# MCU176_2.net
KiCad netlist of a schematic drawn in Altium Designer
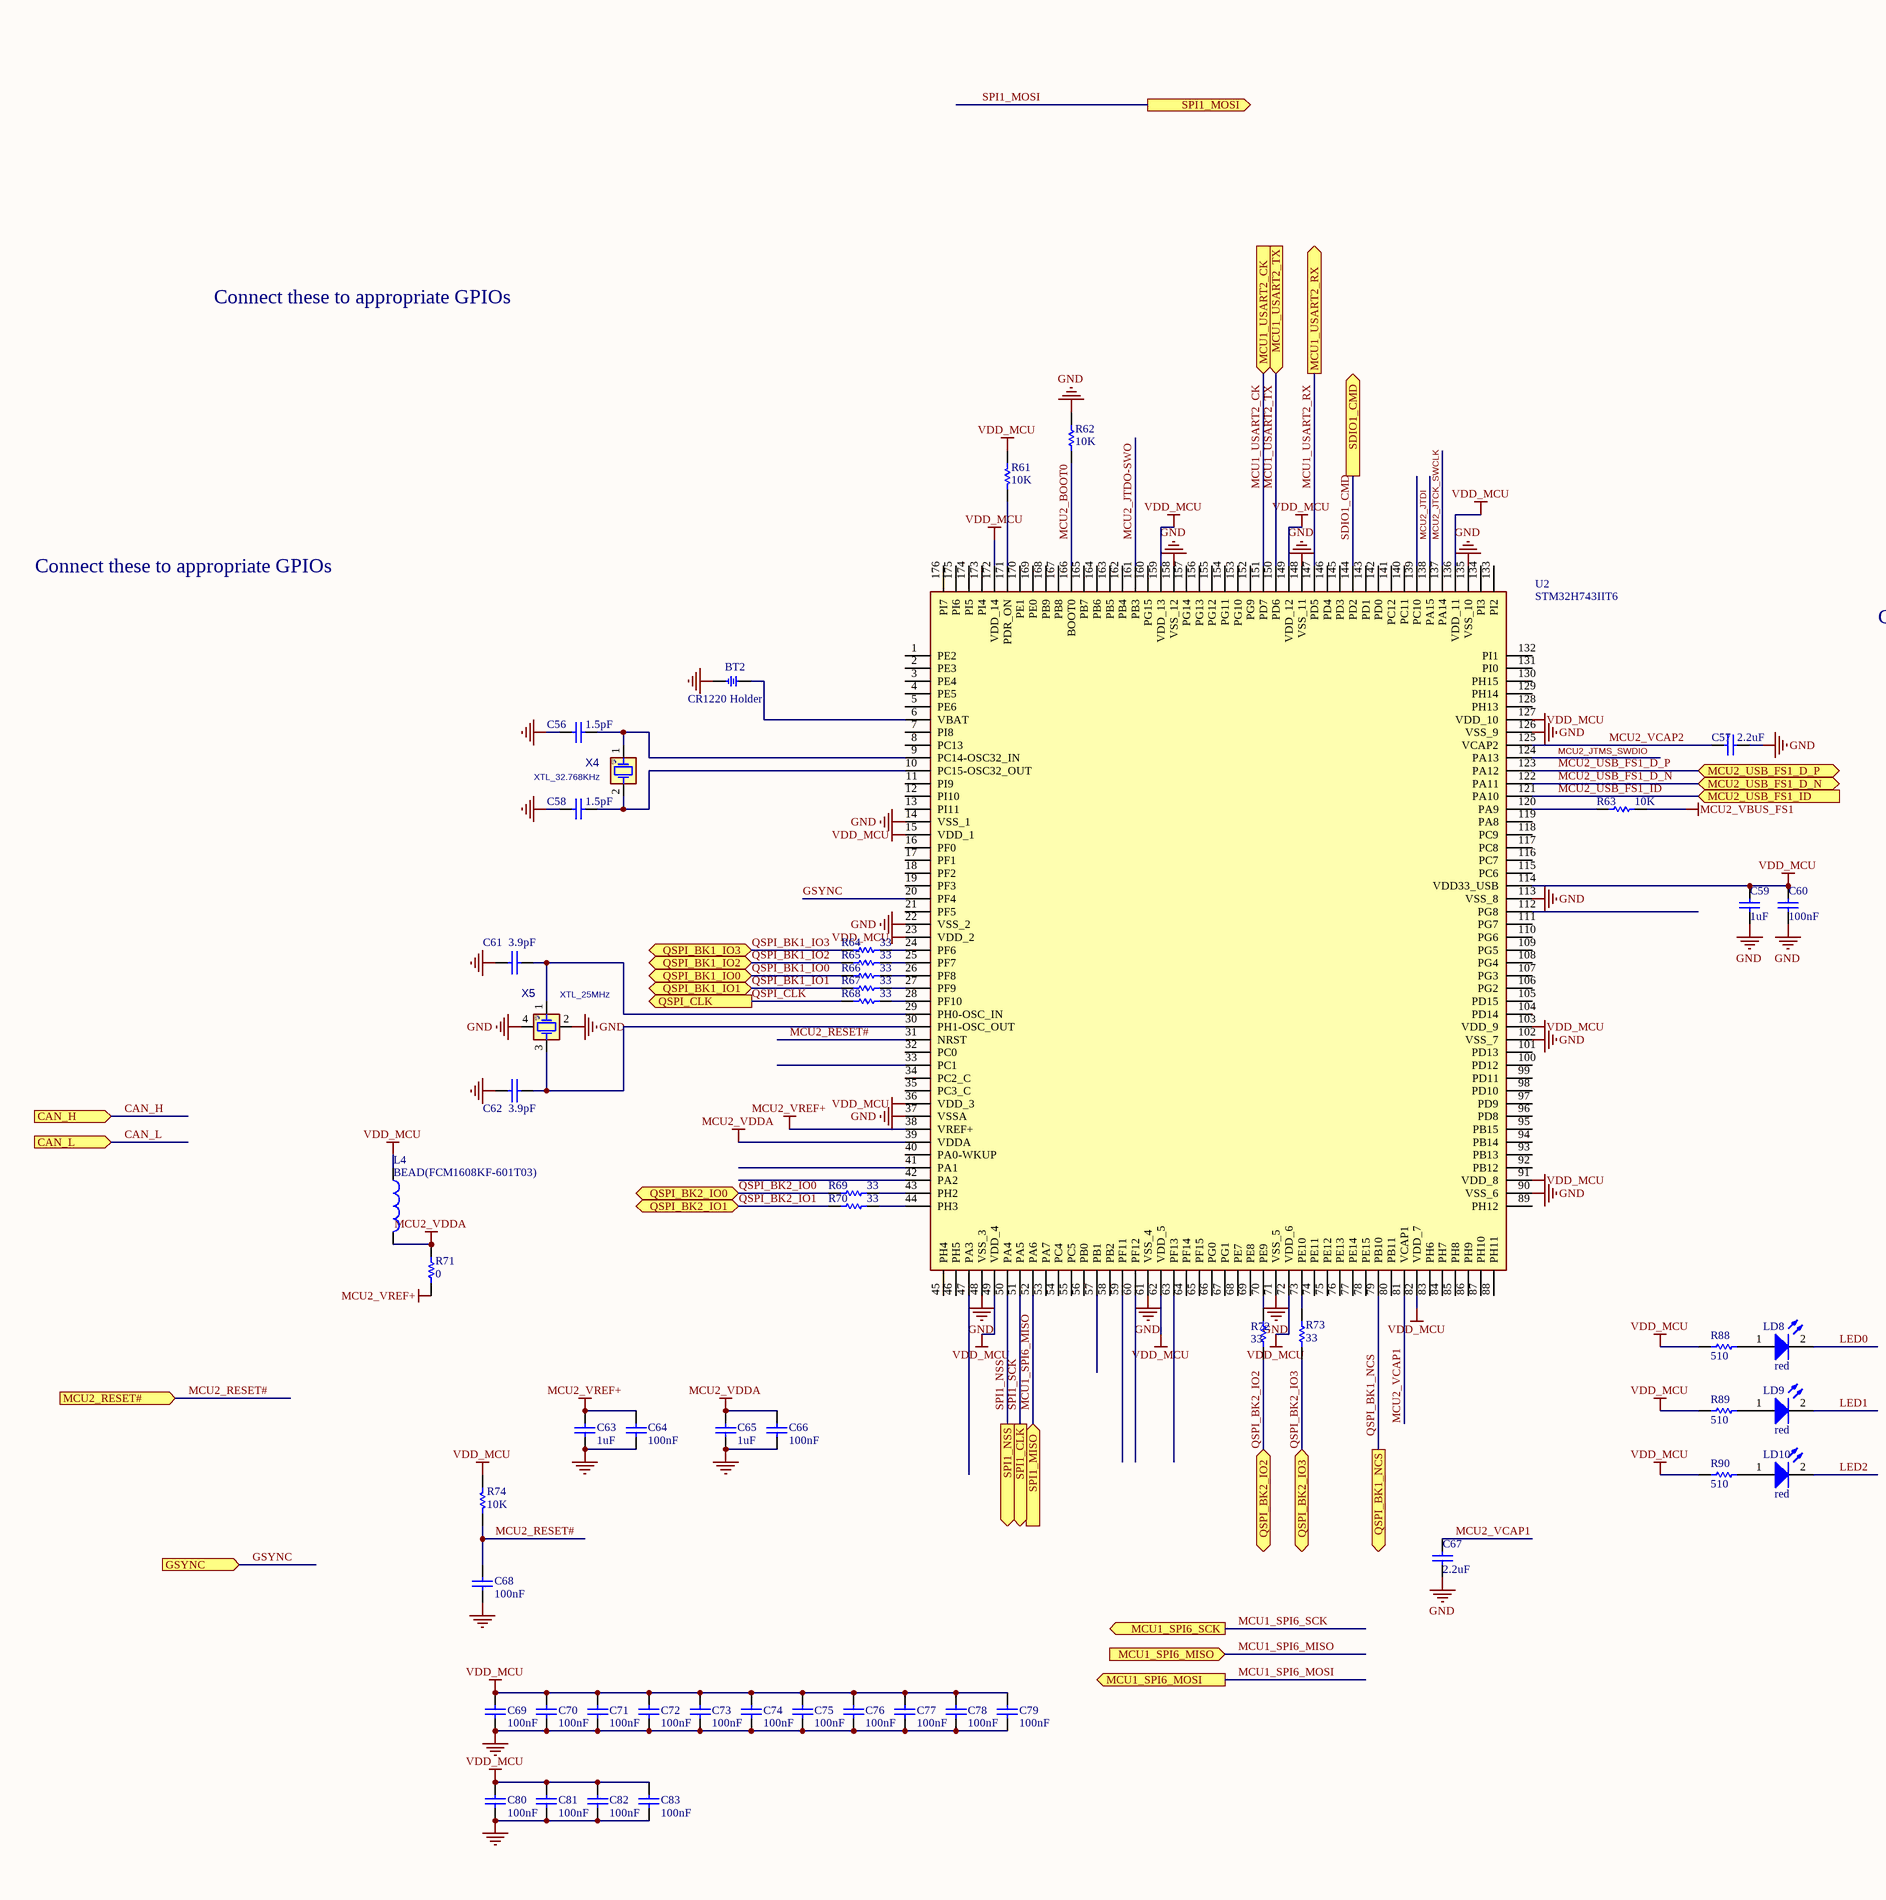
[diagram p0: MCU176_2.SchDoc, left]
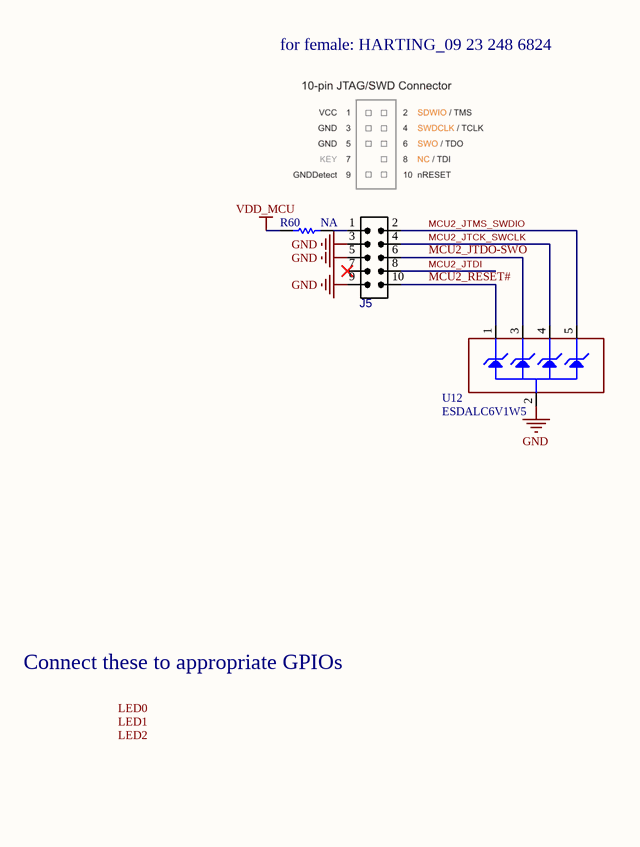
[diagram p1: MCU176_2.SchDoc, right]

(export (version "E")
  (design (tool "Eeschema 10.0.6"))
  (components
    (comp (ref "BT2")
      (value "CR1220 Holder")
      (footprint "BTH1220")
      (description "BATTERY HOLDER, CR1220")
      (libsource (lib "battery") (part "BATH_CR1220"))
    )
    (comp (ref "C56")
      (value "1.5pF")
      (footprint "C0603E")
      (description "Capacitor 0402 / 0603 / 0805")
      (libsource (lib "MCD_TOOLS") (part "Capacitor_ST"))
    )
    (comp (ref "C57")
      (value "2.2uF")
      (footprint "C0603E")
      (description "Capacitor")
      (fields (field (name "PUBLISHER") "Altium Limited"))
      (libsource (lib "Miscellaneous Devices") (part "Cap"))
    )
    (comp (ref "C58")
      (value "1.5pF")
      (footprint "C0603E")
      (description "Capacitor 0402 / 0603 / 0805")
      (libsource (lib "MCD_TOOLS") (part "Capacitor_ST"))
    )
    (comp (ref "C59")
      (value "1uF")
      (footprint "C0603E")
      (description "Capacitor")
      (fields (field (name "PUBLISHER") "Altium Limited"))
      (libsource (lib "Miscellaneous Devices") (part "Cap"))
    )
    (comp (ref "C60")
      (value "100nF")
      (footprint "C0603E")
      (description "Capacitor")
      (fields (field (name "PUBLISHER") "Altium Limited"))
      (libsource (lib "Miscellaneous Devices") (part "Cap"))
    )
    (comp (ref "C61")
      (value "3.9pF")
      (footprint "C0603E")
      (description "Capacitor")
      (libsource (lib "*") (part "CAP"))
    )
    (comp (ref "C62")
      (value "3.9pF")
      (footprint "C0603E")
      (description "Capacitor")
      (libsource (lib "*") (part "CAP"))
    )
    (comp (ref "C63")
      (value "1uF")
      (footprint "C0603E")
      (description "Capacitor")
      (fields (field (name "PUBLISHER") "Altium Limited"))
      (libsource (lib "Miscellaneous Devices") (part "Cap"))
    )
    (comp (ref "C64")
      (value "100nF")
      (footprint "C0603E")
      (description "Capacitor")
      (fields (field (name "PUBLISHER") "Altium Limited"))
      (libsource (lib "Miscellaneous Devices") (part "Cap"))
    )
    (comp (ref "C65")
      (value "1uF")
      (footprint "C0603E")
      (description "Capacitor")
      (fields (field (name "PUBLISHER") "Altium Limited"))
      (libsource (lib "Miscellaneous Devices") (part "Cap"))
    )
    (comp (ref "C66")
      (value "100nF")
      (footprint "C0603E")
      (description "Capacitor")
      (fields (field (name "PUBLISHER") "Altium Limited"))
      (libsource (lib "Miscellaneous Devices") (part "Cap"))
    )
    (comp (ref "C67")
      (value "2.2uF")
      (footprint "C0603E")
      (description "Capacitor")
      (fields (field (name "PUBLISHER") "Altium Limited"))
      (libsource (lib "Miscellaneous Devices") (part "Cap"))
    )
    (comp (ref "C68")
      (value "100nF")
      (footprint "C0603E")
      (description "Capacitor")
      (fields (field (name "PUBLISHER") "Altium Limited"))
      (libsource (lib "Miscellaneous Devices") (part "CAP"))
    )
    (comp (ref "C69")
      (value "100nF")
      (footprint "C0603E")
      (description "Capacitor")
      (fields (field (name "PUBLISHER") "Altium Limited"))
      (libsource (lib "Miscellaneous Devices") (part "CAP"))
    )
    (comp (ref "C70")
      (value "100nF")
      (footprint "C0603E")
      (description "Capacitor")
      (fields (field (name "PUBLISHER") "Altium Limited"))
      (libsource (lib "Miscellaneous Devices") (part "CAP"))
    )
    (comp (ref "C71")
      (value "100nF")
      (footprint "C0603E")
      (description "Capacitor")
      (fields (field (name "PUBLISHER") "Altium Limited"))
      (libsource (lib "Miscellaneous Devices") (part "CAP"))
    )
    (comp (ref "C72")
      (value "100nF")
      (footprint "C0603E")
      (description "Capacitor")
      (fields (field (name "PUBLISHER") "Altium Limited"))
      (libsource (lib "Miscellaneous Devices") (part "CAP"))
    )
    (comp (ref "C73")
      (value "100nF")
      (footprint "C0603E")
      (description "Capacitor")
      (fields (field (name "PUBLISHER") "Altium Limited"))
      (libsource (lib "Miscellaneous Devices") (part "CAP"))
    )
    (comp (ref "C74")
      (value "100nF")
      (footprint "C0603E")
      (description "Capacitor")
      (fields (field (name "PUBLISHER") "Altium Limited"))
      (libsource (lib "Miscellaneous Devices") (part "CAP"))
    )
    (comp (ref "C75")
      (value "100nF")
      (footprint "C0603E")
      (description "Capacitor")
      (fields (field (name "PUBLISHER") "Altium Limited"))
      (libsource (lib "Miscellaneous Devices") (part "CAP"))
    )
    (comp (ref "C76")
      (value "100nF")
      (footprint "C0603E")
      (description "Capacitor")
      (fields (field (name "PUBLISHER") "Altium Limited"))
      (libsource (lib "Miscellaneous Devices") (part "CAP"))
    )
    (comp (ref "C77")
      (value "100nF")
      (footprint "C0603E")
      (description "Capacitor")
      (fields (field (name "PUBLISHER") "Altium Limited"))
      (libsource (lib "Miscellaneous Devices") (part "CAP"))
    )
    (comp (ref "C78")
      (value "100nF")
      (footprint "C0603E")
      (description "Capacitor")
      (fields (field (name "PUBLISHER") "Altium Limited"))
      (libsource (lib "Miscellaneous Devices") (part "CAP"))
    )
    (comp (ref "C79")
      (value "100nF")
      (footprint "C0603E")
      (description "Capacitor")
      (fields (field (name "PUBLISHER") "Altium Limited"))
      (libsource (lib "Miscellaneous Devices") (part "CAP"))
    )
    (comp (ref "C80")
      (value "100nF")
      (footprint "C0603E")
      (description "Capacitor")
      (fields (field (name "PUBLISHER") "Altium Limited"))
      (libsource (lib "Miscellaneous Devices") (part "CAP"))
    )
    (comp (ref "C81")
      (value "100nF")
      (footprint "C0603E")
      (description "Capacitor")
      (fields (field (name "PUBLISHER") "Altium Limited"))
      (libsource (lib "Miscellaneous Devices") (part "CAP"))
    )
    (comp (ref "C82")
      (value "100nF")
      (footprint "C0603E")
      (description "Capacitor")
      (fields (field (name "PUBLISHER") "Altium Limited"))
      (libsource (lib "Miscellaneous Devices") (part "CAP"))
    )
    (comp (ref "C83")
      (value "100nF")
      (footprint "C0603E")
      (description "Capacitor")
      (fields (field (name "PUBLISHER") "Altium Limited"))
      (libsource (lib "Miscellaneous Devices") (part "CAP"))
    )
    (comp (ref "J5")
      (value "IDC_2X5")
      (footprint "IDC_2X5")
      (description "CONN, IDC, Male, pitch: 2.54mm, 10POS")
      (libsource (lib "conn_header_idc") (part "IDC_2X5"))
    )
    (comp (ref "L4")
      (value "BEAD(FCM1608KF-601T03)")
      (footprint "L0603E")
      (description "Inductor")
      (fields (field (name "PUBLISHER") "Altium Limited"))
      (libsource (lib "Miscellaneous Devices") (part "Inductor"))
    )
    (comp (ref "LD8")
      (value "red")
      (footprint "LED0603GRN")
      (description "Typical RED, GREEN, YELLOW, AMBER GaAs LED")
      (fields (field (name "PUBLISHER") "Altium Limited"))
      (libsource (lib "Miscellaneous Devices") (part "LED2"))
    )
    (comp (ref "LD9")
      (value "red")
      (footprint "LED0603GRN")
      (description "Typical RED, GREEN, YELLOW, AMBER GaAs LED")
      (fields (field (name "PUBLISHER") "Altium Limited"))
      (libsource (lib "Miscellaneous Devices") (part "LED2"))
    )
    (comp (ref "LD10")
      (value "red")
      (footprint "LED0603GRN")
      (description "Typical RED, GREEN, YELLOW, AMBER GaAs LED")
      (fields (field (name "PUBLISHER") "Altium Limited"))
      (libsource (lib "Miscellaneous Devices") (part "LED2"))
    )
    (comp (ref "R60")
      (value "NA")
      (footprint "R0603E")
      (description "Resistor")
      (fields (field (name "PUBLISHER") "Altium Limited"))
      (libsource (lib "Miscellaneous Devices") (part "Res1"))
    )
    (comp (ref "R61")
      (value "10K")
      (footprint "R0603E")
      (description "Resistor")
      (fields (field (name "PUBLISHER") "Altium Limited"))
      (libsource (lib "Miscellaneous Devices") (part "Res1"))
    )
    (comp (ref "R62")
      (value "10K")
      (footprint "R0603E")
      (description "Resistor")
      (fields (field (name "PUBLISHER") "Altium Limited"))
      (libsource (lib "Miscellaneous Devices") (part "res1"))
    )
    (comp (ref "R63")
      (value "10K")
      (footprint "R0603E")
      (description "Resistor")
      (fields (field (name "PUBLISHER") "Altium Limited"))
      (libsource (lib "Miscellaneous Devices") (part "Res1"))
    )
    (comp (ref "R64")
      (value "33")
      (footprint "R0603E")
      (description "Resistor")
      (fields (field (name "PUBLISHER") "Altium Limited"))
      (libsource (lib "Miscellaneous Devices") (part "Res1"))
    )
    (comp (ref "R65")
      (value "33")
      (footprint "R0603E")
      (description "Resistor")
      (fields (field (name "PUBLISHER") "Altium Limited"))
      (libsource (lib "Miscellaneous Devices") (part "Res1"))
    )
    (comp (ref "R66")
      (value "33")
      (footprint "R0603E")
      (description "Resistor")
      (fields (field (name "PUBLISHER") "Altium Limited"))
      (libsource (lib "Miscellaneous Devices") (part "Res1"))
    )
    (comp (ref "R67")
      (value "33")
      (footprint "R0603E")
      (description "Resistor")
      (fields (field (name "PUBLISHER") "Altium Limited"))
      (libsource (lib "Miscellaneous Devices") (part "Res1"))
    )
    (comp (ref "R68")
      (value "33")
      (footprint "R0603E")
      (description "Resistor")
      (fields (field (name "PUBLISHER") "Altium Limited"))
      (libsource (lib "Miscellaneous Devices") (part "Res1"))
    )
    (comp (ref "R69")
      (value "33")
      (footprint "R0603E")
      (description "Resistor")
      (fields (field (name "PUBLISHER") "Altium Limited"))
      (libsource (lib "Miscellaneous Devices") (part "Res1"))
    )
    (comp (ref "R70")
      (value "33")
      (footprint "R0603E")
      (description "Resistor")
      (fields (field (name "PUBLISHER") "Altium Limited"))
      (libsource (lib "Miscellaneous Devices") (part "Res1"))
    )
    (comp (ref "R71")
      (value "0")
      (footprint "R0603E")
      (description "Resistor")
      (fields (field (name "PUBLISHER") "Altium Limited"))
      (libsource (lib "Miscellaneous Devices") (part "Res1"))
    )
    (comp (ref "R72")
      (value "33")
      (footprint "R0603E")
      (description "Resistor")
      (fields (field (name "PUBLISHER") "Altium Limited"))
      (libsource (lib "Miscellaneous Devices") (part "Res1"))
    )
    (comp (ref "R73")
      (value "33")
      (footprint "R0603E")
      (description "Resistor")
      (fields (field (name "PUBLISHER") "Altium Limited"))
      (libsource (lib "Miscellaneous Devices") (part "Res1"))
    )
    (comp (ref "R74")
      (value "10K")
      (footprint "R0603E")
      (description "Resistor")
      (fields (field (name "PUBLISHER") "Altium Limited"))
      (libsource (lib "Miscellaneous Devices") (part "Res1"))
    )
    (comp (ref "R88")
      (value "510")
      (footprint "R0603E")
      (description "Resistor")
      (fields (field (name "PUBLISHER") "Altium Limited"))
      (libsource (lib "Miscellaneous Devices") (part "res1"))
    )
    (comp (ref "R89")
      (value "510")
      (footprint "R0603E")
      (description "Resistor")
      (fields (field (name "PUBLISHER") "Altium Limited"))
      (libsource (lib "Miscellaneous Devices") (part "res1"))
    )
    (comp (ref "R90")
      (value "510")
      (footprint "R0603E")
      (description "Resistor")
      (fields (field (name "PUBLISHER") "Altium Limited"))
      (libsource (lib "Miscellaneous Devices") (part "res1"))
    )
    (comp (ref "U2")
      (value "STM32H743IIT6")
      (footprint "SamacSys:QFP50P2600X2600X160-176N")
      (description "Integrated Circuit")
      (fields (field (name "MOUSER PART NUMBER") "511-STM32H743IIT6"))
      (libsource (lib "*") (part "STM32H743IIT6"))
    )
    (comp (ref "U12")
      (value "ESDALC6V1W5")
      (footprint "samacsys:SOT65P210X110-5N")
      (description "Dual Transil array for ESD protection")
      (libsource (lib "MB1167_1") (part "ESDALC6V1W5"))
    )
    (comp (ref "X4")
      (value "XTL_32.768KHz")
      (footprint "XTL_2_1610")
      (description "Crystal")
      (fields (field (name "MANF_P#") "ABS05-32.768KHZ-9-T"))
      (libsource (lib "crystal") (part "XTL_2_32.768_3215A"))
    )
    (comp (ref "X5")
      (value "XTL_25MHz")
      (footprint "XTL_4_2016")
      (description "CRYSTAL")
      (fields (field (name "MANF_P#") "XRCGB25M000F1H00R0"))
      (libsource (lib "crystal") (part "XTL_4_25MHz_3225"))
    )
  )
  (nets
    (net (code "3") (name "/GSYNC") (class "Default")
      (node (ref "U2") (pin "20") (pinfunction "PF4_20") (pintype "passive"))
    )
    (net (code "4") (name "/LED0") (class "Default")
      (node (ref "LD8") (pin "2") (pinfunction "K_2") (pintype "passive"))
    )
    (net (code "5") (name "/LED1") (class "Default")
      (node (ref "LD9") (pin "2") (pinfunction "K_2") (pintype "passive"))
    )
    (net (code "6") (name "/LED2") (class "Default")
      (node (ref "LD10") (pin "2") (pinfunction "K_2") (pintype "passive"))
    )
    (net (code "7") (name "/MCU1_SPI6_MISO") (class "Default")
      (node (ref "U2") (pin "52") (pinfunction "PA6_52") (pintype "passive"))
    )
    (net (code "10") (name "/MCU1_USART2_CK") (class "Default")
      (node (ref "U2") (pin "151") (pinfunction "PD7_151") (pintype "passive"))
    )
    (net (code "11") (name "/MCU1_USART2_RX") (class "Default")
      (node (ref "U2") (pin "147") (pinfunction "PD5_147") (pintype "passive"))
    )
    (net (code "12") (name "/MCU1_USART2_TX") (class "Default")
      (node (ref "U2") (pin "150") (pinfunction "PD6_150") (pintype "passive"))
    )
    (net (code "13") (name "/MCU2_BOOT0") (class "Default")
      (node (ref "R62") (pin "1") (pinfunction "1_1") (pintype "passive"))
      (node (ref "U2") (pin "166") (pinfunction "BOOT0_166") (pintype "passive"))
    )
    (net (code "14") (name "/MCU2_JTCK_SWCLK") (class "Default")
      (node (ref "J5") (pin "4") (pinfunction "4_4") (pintype "passive"))
      (node (ref "U12") (pin "4") (pinfunction "IO3_4") (pintype "passive"))
      (node (ref "U2") (pin "137") (pinfunction "PA14_137") (pintype "passive"))
    )
    (net (code "15") (name "/MCU2_JTDI") (class "Default")
      (node (ref "J5") (pin "8") (pinfunction "8_8") (pintype "passive"))
      (node (ref "U2") (pin "138") (pinfunction "PA15_138") (pintype "passive"))
    )
    (net (code "16") (name "/MCU2_JTDO-SWO") (class "Default")
      (node (ref "J5") (pin "6") (pinfunction "6_6") (pintype "passive"))
      (node (ref "U12") (pin "3") (pinfunction "IO2_3") (pintype "passive"))
      (node (ref "U2") (pin "161") (pinfunction "PB3_161") (pintype "passive"))
    )
    (net (code "17") (name "/MCU2_JTMS_SWDIO") (class "Default")
      (node (ref "J5") (pin "2") (pinfunction "2_2") (pintype "passive"))
      (node (ref "U12") (pin "5") (pinfunction "IO4_5") (pintype "passive"))
      (node (ref "U2") (pin "124") (pinfunction "PA13_124") (pintype "passive"))
    )
    (net (code "18") (name "/MCU2_RESET#") (class "Default")
      (node (ref "C68") (pin "2") (pinfunction "2_2") (pintype "passive"))
      (node (ref "J5") (pin "10") (pinfunction "10_10") (pintype "passive"))
      (node (ref "R74") (pin "2") (pinfunction "2_2") (pintype "passive"))
      (node (ref "U12") (pin "1") (pinfunction "IO1_1") (pintype "passive"))
      (node (ref "U2") (pin "31") (pinfunction "NRST_31") (pintype "passive"))
    )
    (net (code "19") (name "/MCU2_USB_FS1_D_N") (class "Default")
      (node (ref "U2") (pin "122") (pinfunction "PA11_122") (pintype "passive"))
    )
    (net (code "20") (name "/MCU2_USB_FS1_D_P") (class "Default")
      (node (ref "U2") (pin "123") (pinfunction "PA12_123") (pintype "passive"))
    )
    (net (code "21") (name "/MCU2_USB_FS1_ID") (class "Default")
      (node (ref "U2") (pin "121") (pinfunction "PA10_121") (pintype "passive"))
    )
    (net (code "22") (name "/MCU2_VCAP1") (class "Default")
      (node (ref "C67") (pin "2") (pinfunction "2_2") (pintype "passive"))
      (node (ref "U2") (pin "81") (pinfunction "VCAP1_81") (pintype "power_in"))
    )
    (net (code "23") (name "/MCU2_VCAP2") (class "Default")
      (node (ref "C57") (pin "1") (pinfunction "1_1") (pintype "passive"))
      (node (ref "U2") (pin "125") (pinfunction "VCAP2_125") (pintype "power_in"))
    )
    (net (code "24") (name "/QSPI_BK1_IO0") (class "Default")
      (node (ref "R66") (pin "2") (pinfunction "2_2") (pintype "passive"))
    )
    (net (code "25") (name "/QSPI_BK1_IO1") (class "Default")
      (node (ref "R67") (pin "2") (pinfunction "2_2") (pintype "passive"))
    )
    (net (code "26") (name "/QSPI_BK1_IO2") (class "Default")
      (node (ref "R65") (pin "2") (pinfunction "2_2") (pintype "passive"))
    )
    (net (code "27") (name "/QSPI_BK1_IO3") (class "Default")
      (node (ref "R64") (pin "2") (pinfunction "2_2") (pintype "passive"))
    )
    (net (code "28") (name "/QSPI_BK1_NCS") (class "Default")
      (node (ref "U2") (pin "79") (pinfunction "PB10_79") (pintype "passive"))
    )
    (net (code "29") (name "/QSPI_BK2_IO0") (class "Default")
      (node (ref "R69") (pin "2") (pinfunction "2_2") (pintype "passive"))
    )
    (net (code "30") (name "/QSPI_BK2_IO1") (class "Default")
      (node (ref "R70") (pin "2") (pinfunction "2_2") (pintype "passive"))
    )
    (net (code "31") (name "/QSPI_BK2_IO2") (class "Default")
      (node (ref "R72") (pin "2") (pinfunction "2_2") (pintype "passive"))
    )
    (net (code "32") (name "/QSPI_BK2_IO3") (class "Default")
      (node (ref "R73") (pin "2") (pinfunction "2_2") (pintype "passive"))
    )
    (net (code "33") (name "/QSPI_CLK") (class "Default")
      (node (ref "R68") (pin "2") (pinfunction "2_2") (pintype "passive"))
    )
    (net (code "34") (name "/SDIO1_CMD") (class "Default")
      (node (ref "U2") (pin "144") (pinfunction "PD2_144") (pintype "passive"))
    )
    (net (code "36") (name "/SPI1_NSS") (class "Default")
      (node (ref "U2") (pin "50") (pinfunction "PA4_50") (pintype "passive"))
    )
    (net (code "37") (name "/SPI1_SCK") (class "Default")
      (node (ref "U2") (pin "51") (pinfunction "PA5_51") (pintype "passive"))
    )
    (net (code "38") (name "GND") (class "Default")
      (node (ref "BT2") (pin "2") (pinfunction "2_2") (pintype "passive"))
      (node (ref "C56") (pin "2") (pinfunction "2_2") (pintype "passive"))
      (node (ref "C57") (pin "2") (pinfunction "2_2") (pintype "passive"))
      (node (ref "C58") (pin "2") (pinfunction "2_2") (pintype "passive"))
      (node (ref "C59") (pin "1") (pinfunction "1_1") (pintype "passive"))
      (node (ref "C60") (pin "1") (pinfunction "1_1") (pintype "passive"))
      (node (ref "C61") (pin "2") (pinfunction "2_2") (pintype "passive"))
      (node (ref "C62") (pin "2") (pinfunction "2_2") (pintype "passive"))
      (node (ref "C63") (pin "1") (pinfunction "1_1") (pintype "passive"))
      (node (ref "C64") (pin "1") (pinfunction "1_1") (pintype "passive"))
      (node (ref "C65") (pin "1") (pinfunction "1_1") (pintype "passive"))
      (node (ref "C66") (pin "1") (pinfunction "1_1") (pintype "passive"))
      (node (ref "C67") (pin "1") (pinfunction "1_1") (pintype "passive"))
      (node (ref "C68") (pin "1") (pinfunction "1_1") (pintype "passive"))
      (node (ref "C69") (pin "2") (pinfunction "2_2") (pintype "passive"))
      (node (ref "C70") (pin "2") (pinfunction "2_2") (pintype "passive"))
      (node (ref "C71") (pin "2") (pinfunction "2_2") (pintype "passive"))
      (node (ref "C72") (pin "2") (pinfunction "2_2") (pintype "passive"))
      (node (ref "C73") (pin "2") (pinfunction "2_2") (pintype "passive"))
      (node (ref "C74") (pin "2") (pinfunction "2_2") (pintype "passive"))
      (node (ref "C75") (pin "2") (pinfunction "2_2") (pintype "passive"))
      (node (ref "C76") (pin "2") (pinfunction "2_2") (pintype "passive"))
      (node (ref "C77") (pin "2") (pinfunction "2_2") (pintype "passive"))
      (node (ref "C78") (pin "2") (pinfunction "2_2") (pintype "passive"))
      (node (ref "C79") (pin "2") (pinfunction "2_2") (pintype "passive"))
      (node (ref "C80") (pin "2") (pinfunction "2_2") (pintype "passive"))
      (node (ref "C81") (pin "2") (pinfunction "2_2") (pintype "passive"))
      (node (ref "C82") (pin "2") (pinfunction "2_2") (pintype "passive"))
      (node (ref "C83") (pin "2") (pinfunction "2_2") (pintype "passive"))
      (node (ref "J5") (pin "3") (pinfunction "3_3") (pintype "passive"))
      (node (ref "J5") (pin "5") (pinfunction "5_5") (pintype "passive"))
      (node (ref "J5") (pin "9") (pinfunction "9_9") (pintype "passive"))
      (node (ref "R62") (pin "2") (pinfunction "2_2") (pintype "passive"))
      (node (ref "U12") (pin "2") (pinfunction "GND_2") (pintype "passive"))
      (node (ref "U2") (pin "102") (pinfunction "VSS_7_102") (pintype "power_in"))
      (node (ref "U2") (pin "113") (pinfunction "VSS_8_113") (pintype "power_in"))
      (node (ref "U2") (pin "126") (pinfunction "VSS_9_126") (pintype "power_in"))
      (node (ref "U2") (pin "135") (pinfunction "VSS_10_135") (pintype "power_in"))
      (node (ref "U2") (pin "14") (pinfunction "VSS_1_14") (pintype "power_in"))
      (node (ref "U2") (pin "148") (pinfunction "VSS_11_148") (pintype "power_in"))
      (node (ref "U2") (pin "158") (pinfunction "VSS_12_158") (pintype "power_in"))
      (node (ref "U2") (pin "22") (pinfunction "VSS_2_22") (pintype "power_in"))
      (node (ref "U2") (pin "37") (pinfunction "VSSA_37") (pintype "power_in"))
      (node (ref "U2") (pin "48") (pinfunction "VSS_3_48") (pintype "power_in"))
      (node (ref "U2") (pin "61") (pinfunction "VSS_4_61") (pintype "power_in"))
      (node (ref "U2") (pin "71") (pinfunction "VSS_5_71") (pintype "power_in"))
      (node (ref "U2") (pin "90") (pinfunction "VSS_6_90") (pintype "power_in"))
      (node (ref "X5") (pin "2") (pinfunction "GND1_2") (pintype "passive"))
      (node (ref "X5") (pin "4") (pinfunction "GND2_4") (pintype "passive"))
    )
    (net (code "39") (name "MCU2_VBUS_FS1") (class "Default")
      (node (ref "R63") (pin "1") (pinfunction "1_1") (pintype "passive"))
    )
    (net (code "40") (name "MCU2_VDDA") (class "Default")
      (node (ref "C65") (pin "2") (pinfunction "2_2") (pintype "passive"))
      (node (ref "C66") (pin "2") (pinfunction "2_2") (pintype "passive"))
      (node (ref "L4") (pin "2") (pinfunction "2_2") (pintype "passive"))
      (node (ref "R71") (pin "1") (pinfunction "1_1") (pintype "passive"))
      (node (ref "U2") (pin "39") (pinfunction "VDDA_39") (pintype "power_in"))
    )
    (net (code "41") (name "MCU2_VREF+") (class "Default")
      (node (ref "C63") (pin "2") (pinfunction "2_2") (pintype "passive"))
      (node (ref "C64") (pin "2") (pinfunction "2_2") (pintype "passive"))
      (node (ref "R71") (pin "2") (pinfunction "2_2") (pintype "passive"))
      (node (ref "U2") (pin "38") (pinfunction "VREF+_38") (pintype "passive"))
    )
    (net (code "42") (name "Net-(J5-Pad1)") (class "Default")
      (node (ref "J5") (pin "1") (pinfunction "1_1") (pintype "passive"))
      (node (ref "R60") (pin "1") (pinfunction "1_1") (pintype "passive"))
    )
    (net (code "43") (name "Net-(LD8-A)") (class "Default")
      (node (ref "LD8") (pin "1") (pinfunction "A_1") (pintype "passive"))
      (node (ref "R88") (pin "1") (pinfunction "1_1") (pintype "passive"))
    )
    (net (code "44") (name "Net-(LD9-A)") (class "Default")
      (node (ref "LD9") (pin "1") (pinfunction "A_1") (pintype "passive"))
      (node (ref "R89") (pin "1") (pinfunction "1_1") (pintype "passive"))
    )
    (net (code "45") (name "Net-(LD10-A)") (class "Default")
      (node (ref "LD10") (pin "1") (pinfunction "A_1") (pintype "passive"))
      (node (ref "R90") (pin "1") (pinfunction "1_1") (pintype "passive"))
    )
    (net (code "46") (name "Net-(U2-PA9)") (class "Default")
      (node (ref "R63") (pin "2") (pinfunction "2_2") (pintype "passive"))
      (node (ref "U2") (pin "120") (pinfunction "PA9_120") (pintype "passive"))
    )
    (net (code "47") (name "Net-(U2-PC14-OSC32_IN)") (class "Default")
      (node (ref "C56") (pin "1") (pinfunction "1_1") (pintype "passive"))
      (node (ref "U2") (pin "9") (pinfunction "PC14-OSC32_IN_9") (pintype "passive"))
      (node (ref "X4") (pin "1") (pinfunction "OSC1_1") (pintype "passive"))
    )
    (net (code "48") (name "Net-(U2-PC15-OSC32_OUT)") (class "Default")
      (node (ref "C58") (pin "1") (pinfunction "1_1") (pintype "passive"))
      (node (ref "U2") (pin "10") (pinfunction "PC15-OSC32_OUT_10") (pintype "passive"))
      (node (ref "X4") (pin "2") (pinfunction "OSC2_2") (pintype "passive"))
    )
    (net (code "49") (name "Net-(U2-PDR_ON)") (class "Default")
      (node (ref "R61") (pin "2") (pinfunction "2_2") (pintype "passive"))
      (node (ref "U2") (pin "171") (pinfunction "PDR_ON_171") (pintype "passive"))
    )
    (net (code "50") (name "Net-(U2-PE9)") (class "Default")
      (node (ref "R72") (pin "1") (pinfunction "1_1") (pintype "passive"))
      (node (ref "U2") (pin "70") (pinfunction "PE9_70") (pintype "passive"))
    )
    (net (code "51") (name "Net-(U2-PE10)") (class "Default")
      (node (ref "R73") (pin "1") (pinfunction "1_1") (pintype "passive"))
      (node (ref "U2") (pin "73") (pinfunction "PE10_73") (pintype "passive"))
    )
    (net (code "52") (name "Net-(U2-PF6)") (class "Default")
      (node (ref "R64") (pin "1") (pinfunction "1_1") (pintype "passive"))
      (node (ref "U2") (pin "24") (pinfunction "PF6_24") (pintype "passive"))
    )
    (net (code "53") (name "Net-(U2-PF7)") (class "Default")
      (node (ref "R65") (pin "1") (pinfunction "1_1") (pintype "passive"))
      (node (ref "U2") (pin "25") (pinfunction "PF7_25") (pintype "passive"))
    )
    (net (code "54") (name "Net-(U2-PF8)") (class "Default")
      (node (ref "R66") (pin "1") (pinfunction "1_1") (pintype "passive"))
      (node (ref "U2") (pin "26") (pinfunction "PF8_26") (pintype "passive"))
    )
    (net (code "55") (name "Net-(U2-PF9)") (class "Default")
      (node (ref "R67") (pin "1") (pinfunction "1_1") (pintype "passive"))
      (node (ref "U2") (pin "27") (pinfunction "PF9_27") (pintype "passive"))
    )
    (net (code "56") (name "Net-(U2-PF10)") (class "Default")
      (node (ref "R68") (pin "1") (pinfunction "1_1") (pintype "passive"))
      (node (ref "U2") (pin "28") (pinfunction "PF10_28") (pintype "passive"))
    )
    (net (code "57") (name "Net-(U2-PH0-OSC_IN)") (class "Default")
      (node (ref "C61") (pin "1") (pinfunction "1_1") (pintype "passive"))
      (node (ref "U2") (pin "29") (pinfunction "PH0-OSC_IN_29") (pintype "passive"))
      (node (ref "X5") (pin "1") (pinfunction "XA_1") (pintype "passive"))
    )
    (net (code "58") (name "Net-(U2-PH1-OSC_OUT)") (class "Default")
      (node (ref "C62") (pin "1") (pinfunction "1_1") (pintype "passive"))
      (node (ref "U2") (pin "30") (pinfunction "PH1-OSC_OUT_30") (pintype "passive"))
      (node (ref "X5") (pin "3") (pinfunction "XB_3") (pintype "passive"))
    )
    (net (code "59") (name "Net-(U2-PH2)") (class "Default")
      (node (ref "R69") (pin "1") (pinfunction "1_1") (pintype "passive"))
      (node (ref "U2") (pin "43") (pinfunction "PH2_43") (pintype "passive"))
    )
    (net (code "60") (name "Net-(U2-PH3)") (class "Default")
      (node (ref "R70") (pin "1") (pinfunction "1_1") (pintype "passive"))
      (node (ref "U2") (pin "44") (pinfunction "PH3_44") (pintype "passive"))
    )
    (net (code "61") (name "Net-(U2-VBAT)") (class "Default")
      (node (ref "BT2") (pin "1") (pinfunction "1_1") (pintype "passive"))
      (node (ref "U2") (pin "6") (pinfunction "VBAT_6") (pintype "power_in"))
    )
    (net (code "62") (name "VDD_MCU") (class "Default")
      (node (ref "C59") (pin "2") (pinfunction "2_2") (pintype "passive"))
      (node (ref "C60") (pin "2") (pinfunction "2_2") (pintype "passive"))
      (node (ref "C69") (pin "1") (pinfunction "1_1") (pintype "passive"))
      (node (ref "C70") (pin "1") (pinfunction "1_1") (pintype "passive"))
      (node (ref "C71") (pin "1") (pinfunction "1_1") (pintype "passive"))
      (node (ref "C72") (pin "1") (pinfunction "1_1") (pintype "passive"))
      (node (ref "C73") (pin "1") (pinfunction "1_1") (pintype "passive"))
      (node (ref "C74") (pin "1") (pinfunction "1_1") (pintype "passive"))
      (node (ref "C75") (pin "1") (pinfunction "1_1") (pintype "passive"))
      (node (ref "C76") (pin "1") (pinfunction "1_1") (pintype "passive"))
      (node (ref "C77") (pin "1") (pinfunction "1_1") (pintype "passive"))
      (node (ref "C78") (pin "1") (pinfunction "1_1") (pintype "passive"))
      (node (ref "C79") (pin "1") (pinfunction "1_1") (pintype "passive"))
      (node (ref "C80") (pin "1") (pinfunction "1_1") (pintype "passive"))
      (node (ref "C81") (pin "1") (pinfunction "1_1") (pintype "passive"))
      (node (ref "C82") (pin "1") (pinfunction "1_1") (pintype "passive"))
      (node (ref "C83") (pin "1") (pinfunction "1_1") (pintype "passive"))
      (node (ref "L4") (pin "1") (pinfunction "1_1") (pintype "passive"))
      (node (ref "R60") (pin "2") (pinfunction "2_2") (pintype "passive"))
      (node (ref "R61") (pin "1") (pinfunction "1_1") (pintype "passive"))
      (node (ref "R74") (pin "1") (pinfunction "1_1") (pintype "passive"))
      (node (ref "R88") (pin "2") (pinfunction "2_2") (pintype "passive"))
      (node (ref "R89") (pin "2") (pinfunction "2_2") (pintype "passive"))
      (node (ref "R90") (pin "2") (pinfunction "2_2") (pintype "passive"))
      (node (ref "U2") (pin "103") (pinfunction "VDD_9_103") (pintype "power_in"))
      (node (ref "U2") (pin "114") (pinfunction "VDD33_USB_114") (pintype "power_in"))
      (node (ref "U2") (pin "127") (pinfunction "VDD_10_127") (pintype "power_in"))
      (node (ref "U2") (pin "136") (pinfunction "VDD_11_136") (pintype "power_in"))
      (node (ref "U2") (pin "149") (pinfunction "VDD_12_149") (pintype "power_in"))
      (node (ref "U2") (pin "15") (pinfunction "VDD_1_15") (pintype "power_in"))
      (node (ref "U2") (pin "159") (pinfunction "VDD_13_159") (pintype "power_in"))
      (node (ref "U2") (pin "172") (pinfunction "VDD_14_172") (pintype "power_in"))
      (node (ref "U2") (pin "23") (pinfunction "VDD_2_23") (pintype "power_in"))
      (node (ref "U2") (pin "36") (pinfunction "VDD_3_36") (pintype "power_in"))
      (node (ref "U2") (pin "49") (pinfunction "VDD_4_49") (pintype "power_in"))
      (node (ref "U2") (pin "62") (pinfunction "VDD_5_62") (pintype "power_in"))
      (node (ref "U2") (pin "72") (pinfunction "VDD_6_72") (pintype "power_in"))
      (node (ref "U2") (pin "82") (pinfunction "VDD_7_82") (pintype "power_in"))
      (node (ref "U2") (pin "91") (pinfunction "VDD_8_91") (pintype "power_in"))
    )
    (net (code "63") (name "unconnected-(J5-Pad7)") (class "Default")
      (node (ref "J5") (pin "7") (pinfunction "7_7") (pintype "passive+no_connect"))
    )
    (net (code "64") (name "unconnected-(U2-PA0-WKUP-Pad40)") (class "Default")
      (node (ref "U2") (pin "40") (pinfunction "PA0-WKUP_40") (pintype "passive"))
    )
    (net (code "65") (name "unconnected-(U2-PA1-Pad41)") (class "Default")
      (node (ref "U2") (pin "41") (pinfunction "PA1_41") (pintype "passive"))
    )
    (net (code "66") (name "unconnected-(U2-PA2-Pad42)") (class "Default")
      (node (ref "U2") (pin "42") (pinfunction "PA2_42") (pintype "passive"))
    )
    (net (code "67") (name "unconnected-(U2-PA3-Pad47)") (class "Default")
      (node (ref "U2") (pin "47") (pinfunction "PA3_47") (pintype "passive"))
    )
    (net (code "68") (name "unconnected-(U2-PA7-Pad53)") (class "Default")
      (node (ref "U2") (pin "53") (pinfunction "PA7_53") (pintype "passive"))
    )
    (net (code "69") (name "unconnected-(U2-PA8-Pad119)") (class "Default")
      (node (ref "U2") (pin "119") (pinfunction "PA8_119") (pintype "passive"))
    )
    (net (code "70") (name "unconnected-(U2-PB0-Pad56)") (class "Default")
      (node (ref "U2") (pin "56") (pinfunction "PB0_56") (pintype "passive"))
    )
    (net (code "71") (name "unconnected-(U2-PB1-Pad57)") (class "Default")
      (node (ref "U2") (pin "57") (pinfunction "PB1_57") (pintype "passive"))
    )
    (net (code "72") (name "unconnected-(U2-PB2-Pad58)") (class "Default")
      (node (ref "U2") (pin "58") (pinfunction "PB2_58") (pintype "passive"))
    )
    (net (code "73") (name "unconnected-(U2-PB4-Pad162)") (class "Default")
      (node (ref "U2") (pin "162") (pinfunction "PB4_162") (pintype "passive"))
    )
    (net (code "74") (name "unconnected-(U2-PB5-Pad163)") (class "Default")
      (node (ref "U2") (pin "163") (pinfunction "PB5_163") (pintype "passive"))
    )
    (net (code "75") (name "unconnected-(U2-PB6-Pad164)") (class "Default")
      (node (ref "U2") (pin "164") (pinfunction "PB6_164") (pintype "passive"))
    )
    (net (code "76") (name "unconnected-(U2-PB7-Pad165)") (class "Default")
      (node (ref "U2") (pin "165") (pinfunction "PB7_165") (pintype "passive"))
    )
    (net (code "77") (name "unconnected-(U2-PB8-Pad167)") (class "Default")
      (node (ref "U2") (pin "167") (pinfunction "PB8_167") (pintype "passive"))
    )
    (net (code "78") (name "unconnected-(U2-PB9-Pad168)") (class "Default")
      (node (ref "U2") (pin "168") (pinfunction "PB9_168") (pintype "passive"))
    )
    (net (code "79") (name "unconnected-(U2-PB11-Pad80)") (class "Default")
      (node (ref "U2") (pin "80") (pinfunction "PB11_80") (pintype "passive"))
    )
    (net (code "80") (name "unconnected-(U2-PB12-Pad92)") (class "Default")
      (node (ref "U2") (pin "92") (pinfunction "PB12_92") (pintype "passive"))
    )
    (net (code "81") (name "unconnected-(U2-PB13-Pad93)") (class "Default")
      (node (ref "U2") (pin "93") (pinfunction "PB13_93") (pintype "passive"))
    )
    (net (code "82") (name "unconnected-(U2-PB14-Pad94)") (class "Default")
      (node (ref "U2") (pin "94") (pinfunction "PB14_94") (pintype "passive"))
    )
    (net (code "83") (name "unconnected-(U2-PB15-Pad95)") (class "Default")
      (node (ref "U2") (pin "95") (pinfunction "PB15_95") (pintype "passive"))
    )
    (net (code "84") (name "unconnected-(U2-PC0-Pad32)") (class "Default")
      (node (ref "U2") (pin "32") (pinfunction "PC0_32") (pintype "passive"))
    )
    (net (code "85") (name "unconnected-(U2-PC1-Pad33)") (class "Default")
      (node (ref "U2") (pin "33") (pinfunction "PC1_33") (pintype "passive"))
    )
    (net (code "86") (name "unconnected-(U2-PC2_C-Pad34)") (class "Default")
      (node (ref "U2") (pin "34") (pinfunction "PC2_C_34") (pintype "passive"))
    )
    (net (code "87") (name "unconnected-(U2-PC3_C-Pad35)") (class "Default")
      (node (ref "U2") (pin "35") (pinfunction "PC3_C_35") (pintype "passive"))
    )
    (net (code "88") (name "unconnected-(U2-PC4-Pad54)") (class "Default")
      (node (ref "U2") (pin "54") (pinfunction "PC4_54") (pintype "passive"))
    )
    (net (code "89") (name "unconnected-(U2-PC5-Pad55)") (class "Default")
      (node (ref "U2") (pin "55") (pinfunction "PC5_55") (pintype "passive"))
    )
    (net (code "90") (name "unconnected-(U2-PC6-Pad115)") (class "Default")
      (node (ref "U2") (pin "115") (pinfunction "PC6_115") (pintype "passive"))
    )
    (net (code "91") (name "unconnected-(U2-PC7-Pad116)") (class "Default")
      (node (ref "U2") (pin "116") (pinfunction "PC7_116") (pintype "passive"))
    )
    (net (code "92") (name "unconnected-(U2-PC8-Pad117)") (class "Default")
      (node (ref "U2") (pin "117") (pinfunction "PC8_117") (pintype "passive"))
    )
    (net (code "93") (name "unconnected-(U2-PC9-Pad118)") (class "Default")
      (node (ref "U2") (pin "118") (pinfunction "PC9_118") (pintype "passive"))
    )
    (net (code "94") (name "unconnected-(U2-PC10-Pad139)") (class "Default")
      (node (ref "U2") (pin "139") (pinfunction "PC10_139") (pintype "passive"))
    )
    (net (code "95") (name "unconnected-(U2-PC11-Pad140)") (class "Default")
      (node (ref "U2") (pin "140") (pinfunction "PC11_140") (pintype "passive"))
    )
    (net (code "96") (name "unconnected-(U2-PC12-Pad141)") (class "Default")
      (node (ref "U2") (pin "141") (pinfunction "PC12_141") (pintype "passive"))
    )
    (net (code "97") (name "unconnected-(U2-PC13-Pad8)") (class "Default")
      (node (ref "U2") (pin "8") (pinfunction "PC13_8") (pintype "passive"))
    )
    (net (code "98") (name "unconnected-(U2-PD0-Pad142)") (class "Default")
      (node (ref "U2") (pin "142") (pinfunction "PD0_142") (pintype "passive"))
    )
    (net (code "99") (name "unconnected-(U2-PD1-Pad143)") (class "Default")
      (node (ref "U2") (pin "143") (pinfunction "PD1_143") (pintype "passive"))
    )
    (net (code "100") (name "unconnected-(U2-PD3-Pad145)") (class "Default")
      (node (ref "U2") (pin "145") (pinfunction "PD3_145") (pintype "passive"))
    )
    (net (code "101") (name "unconnected-(U2-PD4-Pad146)") (class "Default")
      (node (ref "U2") (pin "146") (pinfunction "PD4_146") (pintype "passive"))
    )
    (net (code "102") (name "unconnected-(U2-PD8-Pad96)") (class "Default")
      (node (ref "U2") (pin "96") (pinfunction "PD8_96") (pintype "passive"))
    )
    (net (code "103") (name "unconnected-(U2-PD9-Pad97)") (class "Default")
      (node (ref "U2") (pin "97") (pinfunction "PD9_97") (pintype "passive"))
    )
    (net (code "104") (name "unconnected-(U2-PD10-Pad98)") (class "Default")
      (node (ref "U2") (pin "98") (pinfunction "PD10_98") (pintype "passive"))
    )
    (net (code "105") (name "unconnected-(U2-PD11-Pad99)") (class "Default")
      (node (ref "U2") (pin "99") (pinfunction "PD11_99") (pintype "passive"))
    )
    (net (code "106") (name "unconnected-(U2-PD12-Pad100)") (class "Default")
      (node (ref "U2") (pin "100") (pinfunction "PD12_100") (pintype "passive"))
    )
    (net (code "107") (name "unconnected-(U2-PD13-Pad101)") (class "Default")
      (node (ref "U2") (pin "101") (pinfunction "PD13_101") (pintype "passive"))
    )
    (net (code "108") (name "unconnected-(U2-PD14-Pad104)") (class "Default")
      (node (ref "U2") (pin "104") (pinfunction "PD14_104") (pintype "passive"))
    )
    (net (code "109") (name "unconnected-(U2-PD15-Pad105)") (class "Default")
      (node (ref "U2") (pin "105") (pinfunction "PD15_105") (pintype "passive"))
    )
    (net (code "110") (name "unconnected-(U2-PE0-Pad169)") (class "Default")
      (node (ref "U2") (pin "169") (pinfunction "PE0_169") (pintype "passive"))
    )
    (net (code "111") (name "unconnected-(U2-PE1-Pad170)") (class "Default")
      (node (ref "U2") (pin "170") (pinfunction "PE1_170") (pintype "passive"))
    )
    (net (code "112") (name "unconnected-(U2-PE2-Pad1)") (class "Default")
      (node (ref "U2") (pin "1") (pinfunction "PE2_1") (pintype "passive"))
    )
    (net (code "113") (name "unconnected-(U2-PE3-Pad2)") (class "Default")
      (node (ref "U2") (pin "2") (pinfunction "PE3_2") (pintype "passive"))
    )
    (net (code "114") (name "unconnected-(U2-PE4-Pad3)") (class "Default")
      (node (ref "U2") (pin "3") (pinfunction "PE4_3") (pintype "passive"))
    )
    (net (code "115") (name "unconnected-(U2-PE5-Pad4)") (class "Default")
      (node (ref "U2") (pin "4") (pinfunction "PE5_4") (pintype "passive"))
    )
    (net (code "116") (name "unconnected-(U2-PE6-Pad5)") (class "Default")
      (node (ref "U2") (pin "5") (pinfunction "PE6_5") (pintype "passive"))
    )
    (net (code "117") (name "unconnected-(U2-PE7-Pad68)") (class "Default")
      (node (ref "U2") (pin "68") (pinfunction "PE7_68") (pintype "passive"))
    )
    (net (code "118") (name "unconnected-(U2-PE8-Pad69)") (class "Default")
      (node (ref "U2") (pin "69") (pinfunction "PE8_69") (pintype "passive"))
    )
    (net (code "119") (name "unconnected-(U2-PE11-Pad74)") (class "Default")
      (node (ref "U2") (pin "74") (pinfunction "PE11_74") (pintype "passive"))
    )
    (net (code "120") (name "unconnected-(U2-PE12-Pad75)") (class "Default")
      (node (ref "U2") (pin "75") (pinfunction "PE12_75") (pintype "passive"))
    )
    (net (code "121") (name "unconnected-(U2-PE13-Pad76)") (class "Default")
      (node (ref "U2") (pin "76") (pinfunction "PE13_76") (pintype "passive"))
    )
    (net (code "122") (name "unconnected-(U2-PE14-Pad77)") (class "Default")
      (node (ref "U2") (pin "77") (pinfunction "PE14_77") (pintype "passive"))
    )
    (net (code "123") (name "unconnected-(U2-PE15-Pad78)") (class "Default")
      (node (ref "U2") (pin "78") (pinfunction "PE15_78") (pintype "passive"))
    )
    (net (code "124") (name "unconnected-(U2-PF0-Pad16)") (class "Default")
      (node (ref "U2") (pin "16") (pinfunction "PF0_16") (pintype "passive"))
    )
    (net (code "125") (name "unconnected-(U2-PF1-Pad17)") (class "Default")
      (node (ref "U2") (pin "17") (pinfunction "PF1_17") (pintype "passive"))
    )
    (net (code "126") (name "unconnected-(U2-PF2-Pad18)") (class "Default")
      (node (ref "U2") (pin "18") (pinfunction "PF2_18") (pintype "passive"))
    )
    (net (code "127") (name "unconnected-(U2-PF3-Pad19)") (class "Default")
      (node (ref "U2") (pin "19") (pinfunction "PF3_19") (pintype "passive"))
    )
    (net (code "128") (name "unconnected-(U2-PF5-Pad21)") (class "Default")
      (node (ref "U2") (pin "21") (pinfunction "PF5_21") (pintype "passive"))
    )
    (net (code "129") (name "unconnected-(U2-PF11-Pad59)") (class "Default")
      (node (ref "U2") (pin "59") (pinfunction "PF11_59") (pintype "passive"))
    )
    (net (code "130") (name "unconnected-(U2-PF12-Pad60)") (class "Default")
      (node (ref "U2") (pin "60") (pinfunction "PF12_60") (pintype "passive"))
    )
    (net (code "131") (name "unconnected-(U2-PF13-Pad63)") (class "Default")
      (node (ref "U2") (pin "63") (pinfunction "PF13_63") (pintype "passive"))
    )
    (net (code "132") (name "unconnected-(U2-PF14-Pad64)") (class "Default")
      (node (ref "U2") (pin "64") (pinfunction "PF14_64") (pintype "passive"))
    )
    (net (code "133") (name "unconnected-(U2-PF15-Pad65)") (class "Default")
      (node (ref "U2") (pin "65") (pinfunction "PF15_65") (pintype "passive"))
    )
    (net (code "134") (name "unconnected-(U2-PG0-Pad66)") (class "Default")
      (node (ref "U2") (pin "66") (pinfunction "PG0_66") (pintype "passive"))
    )
    (net (code "135") (name "unconnected-(U2-PG1-Pad67)") (class "Default")
      (node (ref "U2") (pin "67") (pinfunction "PG1_67") (pintype "passive"))
    )
    (net (code "136") (name "unconnected-(U2-PG2-Pad106)") (class "Default")
      (node (ref "U2") (pin "106") (pinfunction "PG2_106") (pintype "passive"))
    )
    (net (code "137") (name "unconnected-(U2-PG3-Pad107)") (class "Default")
      (node (ref "U2") (pin "107") (pinfunction "PG3_107") (pintype "passive"))
    )
    (net (code "138") (name "unconnected-(U2-PG4-Pad108)") (class "Default")
      (node (ref "U2") (pin "108") (pinfunction "PG4_108") (pintype "passive"))
    )
    (net (code "139") (name "unconnected-(U2-PG5-Pad109)") (class "Default")
      (node (ref "U2") (pin "109") (pinfunction "PG5_109") (pintype "passive"))
    )
    (net (code "140") (name "unconnected-(U2-PG6-Pad110)") (class "Default")
      (node (ref "U2") (pin "110") (pinfunction "PG6_110") (pintype "passive"))
    )
    (net (code "141") (name "unconnected-(U2-PG7-Pad111)") (class "Default")
      (node (ref "U2") (pin "111") (pinfunction "PG7_111") (pintype "passive"))
    )
    (net (code "142") (name "unconnected-(U2-PG8-Pad112)") (class "Default")
      (node (ref "U2") (pin "112") (pinfunction "PG8_112") (pintype "passive"))
    )
    (net (code "143") (name "unconnected-(U2-PG9-Pad152)") (class "Default")
      (node (ref "U2") (pin "152") (pinfunction "PG9_152") (pintype "passive"))
    )
    (net (code "144") (name "unconnected-(U2-PG10-Pad153)") (class "Default")
      (node (ref "U2") (pin "153") (pinfunction "PG10_153") (pintype "passive"))
    )
    (net (code "145") (name "unconnected-(U2-PG11-Pad154)") (class "Default")
      (node (ref "U2") (pin "154") (pinfunction "PG11_154") (pintype "passive"))
    )
    (net (code "146") (name "unconnected-(U2-PG12-Pad155)") (class "Default")
      (node (ref "U2") (pin "155") (pinfunction "PG12_155") (pintype "passive"))
    )
    (net (code "147") (name "unconnected-(U2-PG13-Pad156)") (class "Default")
      (node (ref "U2") (pin "156") (pinfunction "PG13_156") (pintype "passive"))
    )
    (net (code "148") (name "unconnected-(U2-PG14-Pad157)") (class "Default")
      (node (ref "U2") (pin "157") (pinfunction "PG14_157") (pintype "passive"))
    )
    (net (code "149") (name "unconnected-(U2-PG15-Pad160)") (class "Default")
      (node (ref "U2") (pin "160") (pinfunction "PG15_160") (pintype "passive"))
    )
    (net (code "150") (name "unconnected-(U2-PH4-Pad45)") (class "Default")
      (node (ref "U2") (pin "45") (pinfunction "PH4_45") (pintype "passive"))
    )
    (net (code "151") (name "unconnected-(U2-PH5-Pad46)") (class "Default")
      (node (ref "U2") (pin "46") (pinfunction "PH5_46") (pintype "passive"))
    )
    (net (code "152") (name "unconnected-(U2-PH6-Pad83)") (class "Default")
      (node (ref "U2") (pin "83") (pinfunction "PH6_83") (pintype "passive"))
    )
    (net (code "153") (name "unconnected-(U2-PH7-Pad84)") (class "Default")
      (node (ref "U2") (pin "84") (pinfunction "PH7_84") (pintype "passive"))
    )
    (net (code "154") (name "unconnected-(U2-PH8-Pad85)") (class "Default")
      (node (ref "U2") (pin "85") (pinfunction "PH8_85") (pintype "passive"))
    )
    (net (code "155") (name "unconnected-(U2-PH9-Pad86)") (class "Default")
      (node (ref "U2") (pin "86") (pinfunction "PH9_86") (pintype "passive"))
    )
    (net (code "156") (name "unconnected-(U2-PH10-Pad87)") (class "Default")
      (node (ref "U2") (pin "87") (pinfunction "PH10_87") (pintype "passive"))
    )
    (net (code "157") (name "unconnected-(U2-PH11-Pad88)") (class "Default")
      (node (ref "U2") (pin "88") (pinfunction "PH11_88") (pintype "passive"))
    )
    (net (code "158") (name "unconnected-(U2-PH12-Pad89)") (class "Default")
      (node (ref "U2") (pin "89") (pinfunction "PH12_89") (pintype "passive"))
    )
    (net (code "159") (name "unconnected-(U2-PH13-Pad128)") (class "Default")
      (node (ref "U2") (pin "128") (pinfunction "PH13_128") (pintype "passive"))
    )
    (net (code "160") (name "unconnected-(U2-PH14-Pad129)") (class "Default")
      (node (ref "U2") (pin "129") (pinfunction "PH14_129") (pintype "passive"))
    )
    (net (code "161") (name "unconnected-(U2-PH15-Pad130)") (class "Default")
      (node (ref "U2") (pin "130") (pinfunction "PH15_130") (pintype "passive"))
    )
    (net (code "162") (name "unconnected-(U2-PI0-Pad131)") (class "Default")
      (node (ref "U2") (pin "131") (pinfunction "PI0_131") (pintype "passive"))
    )
    (net (code "163") (name "unconnected-(U2-PI1-Pad132)") (class "Default")
      (node (ref "U2") (pin "132") (pinfunction "PI1_132") (pintype "passive"))
    )
    (net (code "164") (name "unconnected-(U2-PI2-Pad133)") (class "Default")
      (node (ref "U2") (pin "133") (pinfunction "PI2_133") (pintype "passive"))
    )
    (net (code "165") (name "unconnected-(U2-PI3-Pad134)") (class "Default")
      (node (ref "U2") (pin "134") (pinfunction "PI3_134") (pintype "passive"))
    )
    (net (code "166") (name "unconnected-(U2-PI4-Pad173)") (class "Default")
      (node (ref "U2") (pin "173") (pinfunction "PI4_173") (pintype "passive"))
    )
    (net (code "167") (name "unconnected-(U2-PI5-Pad174)") (class "Default")
      (node (ref "U2") (pin "174") (pinfunction "PI5_174") (pintype "passive"))
    )
    (net (code "168") (name "unconnected-(U2-PI6-Pad175)") (class "Default")
      (node (ref "U2") (pin "175") (pinfunction "PI6_175") (pintype "passive"))
    )
    (net (code "169") (name "unconnected-(U2-PI7-Pad176)") (class "Default")
      (node (ref "U2") (pin "176") (pinfunction "PI7_176") (pintype "passive"))
    )
    (net (code "170") (name "unconnected-(U2-PI8-Pad7)") (class "Default")
      (node (ref "U2") (pin "7") (pinfunction "PI8_7") (pintype "passive"))
    )
    (net (code "171") (name "unconnected-(U2-PI9-Pad11)") (class "Default")
      (node (ref "U2") (pin "11") (pinfunction "PI9_11") (pintype "passive"))
    )
    (net (code "172") (name "unconnected-(U2-PI10-Pad12)") (class "Default")
      (node (ref "U2") (pin "12") (pinfunction "PI10_12") (pintype "passive"))
    )
    (net (code "173") (name "unconnected-(U2-PI11-Pad13)") (class "Default")
      (node (ref "U2") (pin "13") (pinfunction "PI11_13") (pintype "passive"))
    )
  )
)
